# 04-WPT-IC.net
KiCad netlist of a schematic drawn in Altium Designer
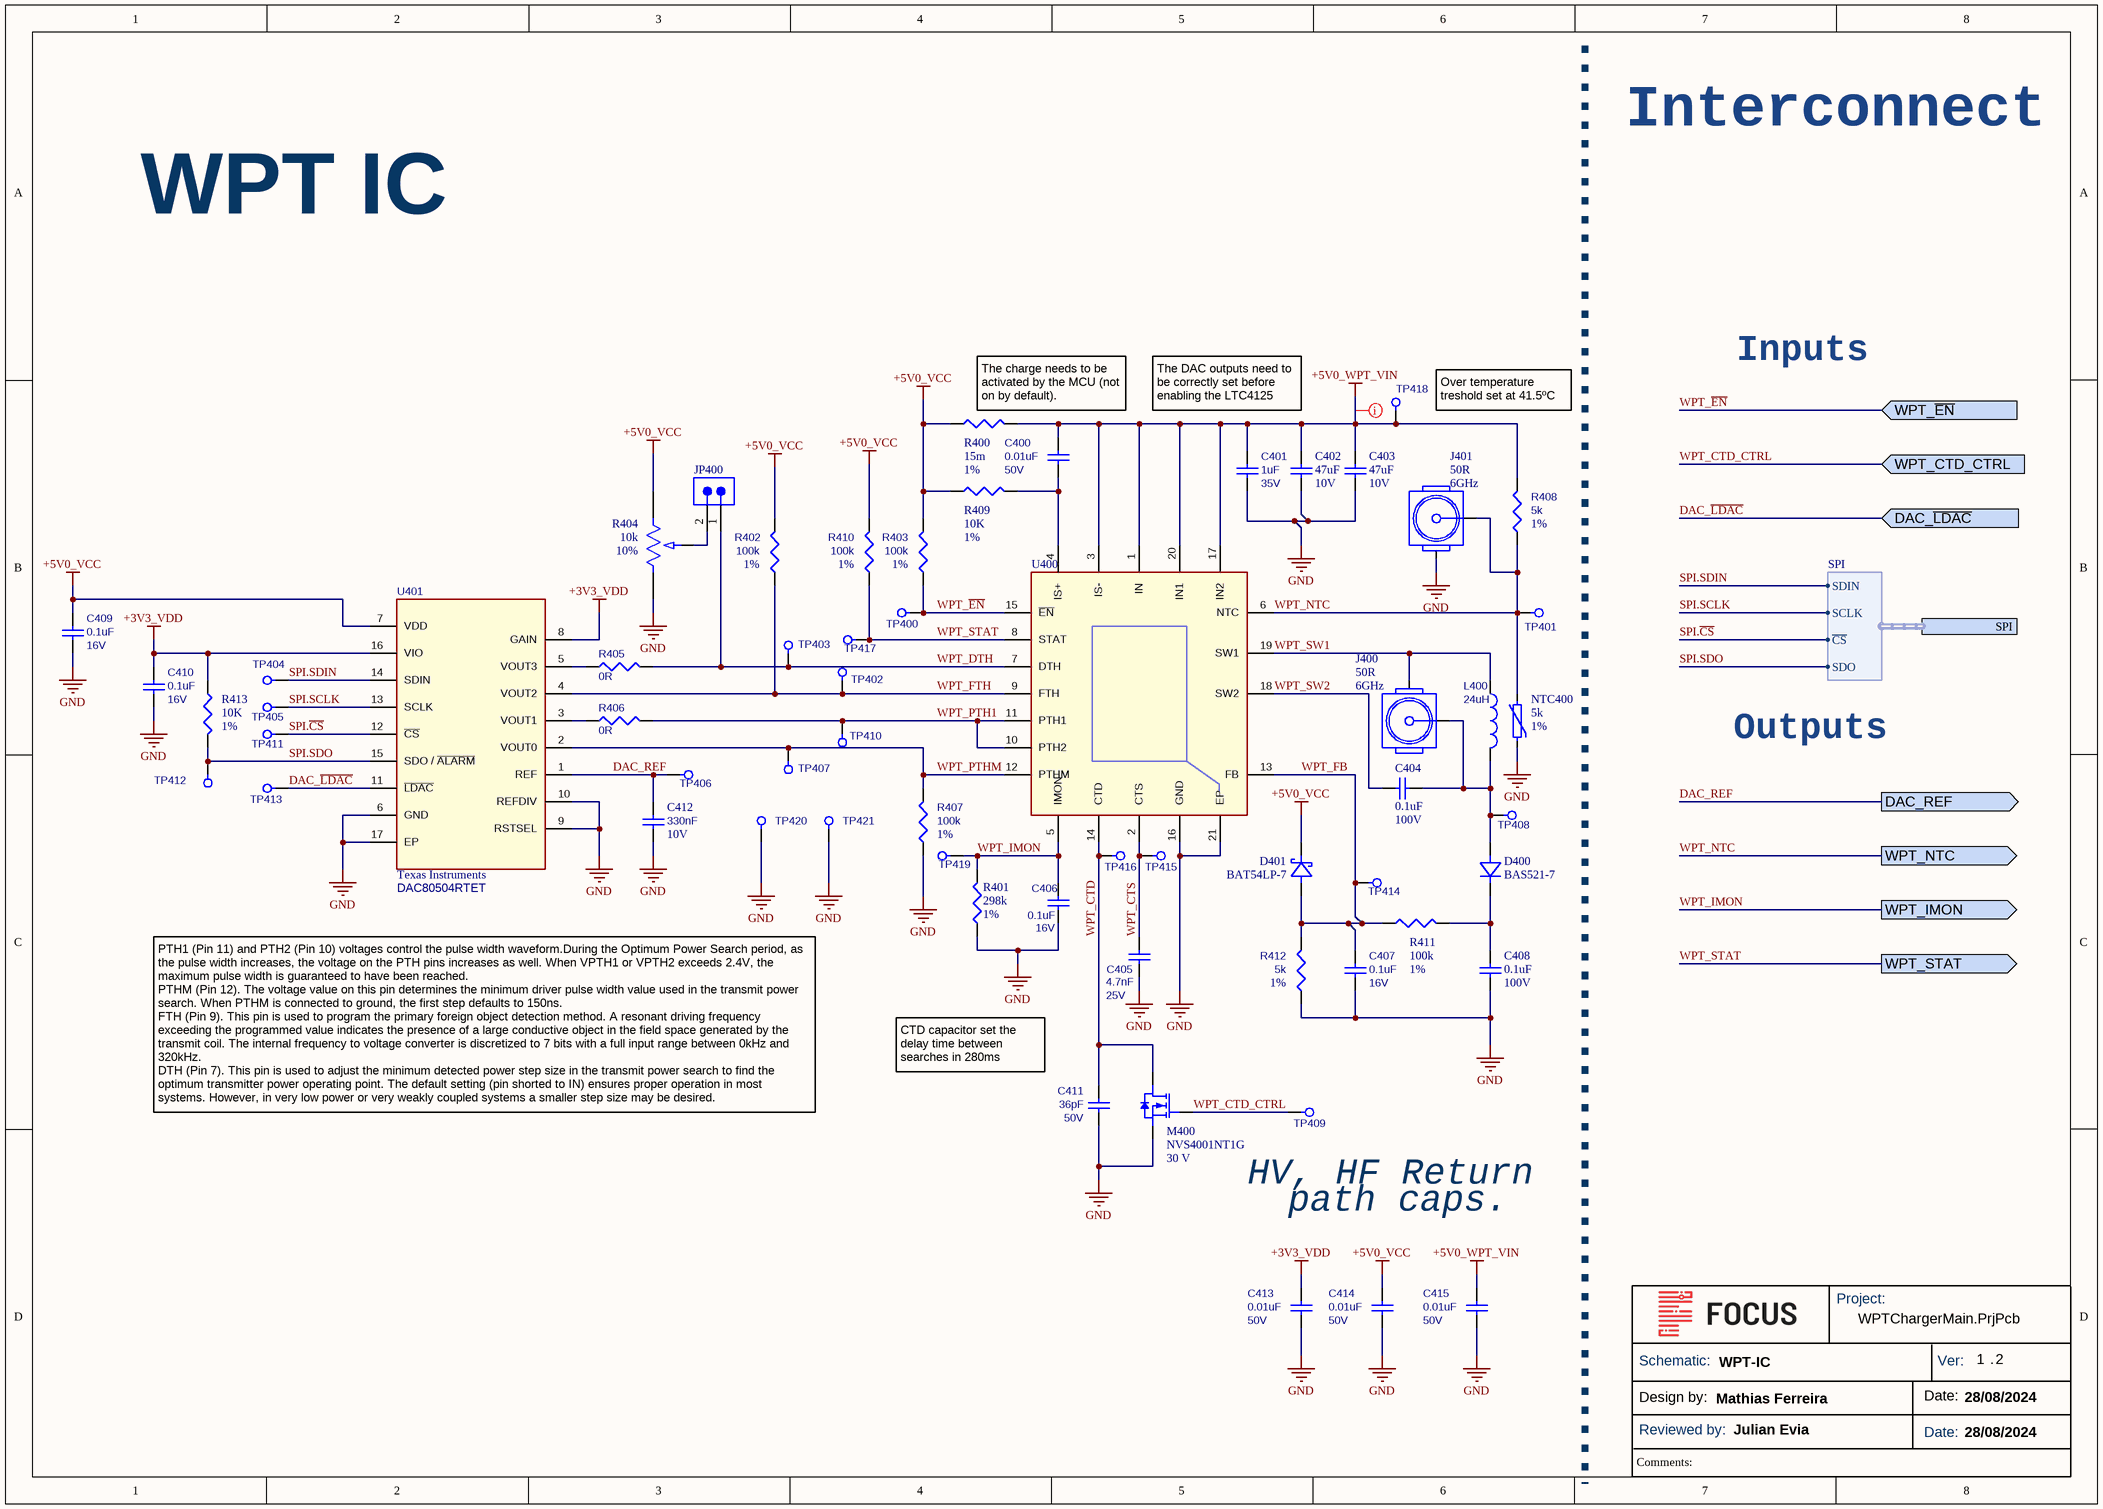
[diagram p0: 04-WPT-IC.SchDoc]

(export (version "E")
  (design (tool "Eeschema 10.0.6"))
  (components
    (comp (ref "C400")
      (value "0.01uF")
      (footprint "C0402")
      (description "Capacitor, 0.01uF, X7R, 50V, 10%, 0402, Implant-grade")
      (fields
        (field (name "MANUFACTURER") "Murata")
        (field (name "RATING") "50V")
        (field (name "MANUFACTURER PART NUMBER") "GCM155R71H103KA55J")
      )
      (libsource (lib "MP-LIBRARY") (part "GCM155R71H103KA55J"))
    )
    (comp (ref "C401")
      (value "1uF")
      (footprint "C0402")
      (description "1 µF ±10% 35V Ceramic Capacitor X5R 0402 (1005 Metric)")
      (fields
        (field (name "MANUFACTURER") "Murata")
        (field (name "MANUFACTURER PART NUMBER") "GRM155R6YA105KE11D")
        (field (name "RATING") "35V")
      )
      (libsource (lib "MP-LIBRARY") (part "GRM155R6YA105KE11D"))
    )
    (comp (ref "C402")
      (value "47uF")
      (footprint "C0805")
      (description "47 µF ±20% 10V Ceramic Capacitor X5R 0805 (2012 Metric)")
      (fields
        (field (name "MANUFACTURER") "Murata")
        (field (name "MANUFACTURER PART NUMBER") "GRM21BR61A476ME15L")
        (field (name "VOLTAGE RATING") "10V")
      )
      (libsource (lib "MP-LIBRARY") (part "GRM21BR61A476ME15L"))
    )
    (comp (ref "C403")
      (value "47uF")
      (footprint "C0805")
      (description "47 µF ±20% 10V Ceramic Capacitor X5R 0805 (2012 Metric)")
      (fields
        (field (name "MANUFACTURER") "Murata")
        (field (name "MANUFACTURER PART NUMBER") "GRM21BR61A476ME15L")
        (field (name "VOLTAGE RATING") "10V")
      )
      (libsource (lib "MP-LIBRARY") (part "GRM21BR61A476ME15L"))
    )
    (comp (ref "C404")
      (value "0.1uF")
      (footprint "C1206")
      (description "0.1 µF ±5% 100V Ceramic Capacitor C0G, NP0 1206 (3216 Metric)")
      (fields
        (field (name "MANUFACTURER") "TDK Corporation")
        (field (name "MANUFACTURER PART NUMBER") "C3216C0G2A104J160AC")
        (field (name "VOLTAGE RATING") "100V")
      )
      (libsource (lib "MP-LIBRARY") (part "C3216C0G2A104J160AC"))
    )
    (comp (ref "C405")
      (value "4.7nF")
      (footprint "C0402")
      (description "4700 pF ±10% 25V Ceramic Capacitor X7R 0402 (1005 Metric)")
      (fields
        (field (name "MANUFACTURER") "Murata")
        (field (name "MANUFACTURER PART NUMBER") "GCM155R71E472KA37D")
        (field (name "RATING") "25V")
      )
      (libsource (lib "MP-LIBRARY") (part "GCM155R71E472KA37D"))
    )
    (comp (ref "C406")
      (value "0.1uF")
      (footprint "C0402")
      (description "Capacitor, 0.1uF, X7R, 16V, 10%, 0402, Implant-grade")
      (fields
        (field (name "MANUFACTURER") "Murata")
        (field (name "MANUFACTURER PART NUMBER") "GCM155R71C104KA55")
        (field (name "RATING") "16V")
      )
      (libsource (lib "MP-LIBRARY") (part "GCM155R71C104KA55"))
    )
    (comp (ref "C407")
      (value "0.1uF")
      (footprint "C0402")
      (description "Capacitor, 0.1uF, X7R, 16V, 10%, 0402, Implant-grade")
      (fields
        (field (name "MANUFACTURER") "Murata")
        (field (name "MANUFACTURER PART NUMBER") "GCM155R71C104KA55")
        (field (name "RATING") "16V")
      )
      (libsource (lib "MP-LIBRARY") (part "GCM155R71C104KA55"))
    )
    (comp (ref "C408")
      (value "0.1uF")
      (footprint "C1206")
      (description "0.1 µF ±5% 100V Ceramic Capacitor C0G, NP0 1206 (3216 Metric)")
      (fields
        (field (name "MANUFACTURER") "TDK Corporation")
        (field (name "MANUFACTURER PART NUMBER") "C3216C0G2A104J160AC")
        (field (name "VOLTAGE RATING") "100V")
      )
      (libsource (lib "MP-LIBRARY") (part "C3216C0G2A104J160AC"))
    )
    (comp (ref "C409")
      (value "0.1uF")
      (footprint "C0402")
      (description "Capacitor, 0.1uF, X7R, 16V, 10%, 0402, Implant-grade")
      (fields
        (field (name "MANUFACTURER") "Murata")
        (field (name "MANUFACTURER PART NUMBER") "GCM155R71C104KA55")
        (field (name "RATING") "16V")
      )
      (libsource (lib "MP-LIBRARY") (part "GCM155R71C104KA55"))
    )
    (comp (ref "C410")
      (value "0.1uF")
      (footprint "C0402")
      (description "Capacitor, 0.1uF, X7R, 16V, 10%, 0402, Implant-grade")
      (fields
        (field (name "MANUFACTURER") "Murata")
        (field (name "MANUFACTURER PART NUMBER") "GCM155R71C104KA55")
        (field (name "RATING") "16V")
      )
      (libsource (lib "MP-LIBRARY") (part "GCM155R71C104KA55"))
    )
    (comp (ref "C411")
      (value "36pF")
      (footprint "C0402")
      (description "36 pF ±1% 50V Ceramic Capacitor C0G, NP0 0402 (1005 Metric)")
      (fields
        (field (name "MANUFACTURER") "Murata")
        (field (name "MANUFACTURER PART NUMBER") "GCM1555C1H360FA16D")
        (field (name "RATING") "50V")
      )
      (libsource (lib "MP-LIBRARY") (part "GCM1555C1H360FA16D"))
    )
    (comp (ref "C412")
      (value "330nF")
      (footprint "C0402")
      (fields
        (field (name "MANUFACTURER") "Murata")
        (field (name "MANUFACTURER PART NUMBER") "GRM155R61A334KE15D")
        (field (name "RATED DC VOLTAGE (URDC)") "10V")
      )
      (libsource (lib "MP-LIBRARY") (part "GRM155R61A334KE15D"))
    )
    (comp (ref "C413")
      (value "0.01uF")
      (footprint "C0402")
      (description "Capacitor, 0.01uF, X7R, 50V, 10%, 0402, Implant-grade")
      (fields
        (field (name "MANUFACTURER") "Murata")
        (field (name "RATING") "50V")
        (field (name "MANUFACTURER PART NUMBER") "GCM155R71H103KA55J")
      )
      (libsource (lib "MP-LIBRARY") (part "GCM155R71H103KA55J"))
    )
    (comp (ref "C414")
      (value "0.01uF")
      (footprint "C0402")
      (description "Capacitor, 0.01uF, X7R, 50V, 10%, 0402, Implant-grade")
      (fields
        (field (name "MANUFACTURER") "Murata")
        (field (name "RATING") "50V")
        (field (name "MANUFACTURER PART NUMBER") "GCM155R71H103KA55J")
      )
      (libsource (lib "MP-LIBRARY") (part "GCM155R71H103KA55J"))
    )
    (comp (ref "C415")
      (value "0.01uF")
      (footprint "C0402")
      (description "Capacitor, 0.01uF, X7R, 50V, 10%, 0402, Implant-grade")
      (fields
        (field (name "MANUFACTURER") "Murata")
        (field (name "RATING") "50V")
        (field (name "MANUFACTURER PART NUMBER") "GCM155R71H103KA55J")
      )
      (libsource (lib "MP-LIBRARY") (part "GCM155R71H103KA55J"))
    )
    (comp (ref "D400")
      (value "BAS521-7")
      (footprint "BAS521_SOD523")
      (description "Diode 300 V 250mA Surface Mount SOD-523")
      (fields (field (name "MANUFACTURER") "Diodes Incorporated"))
      (libsource (lib "MP-LIBRARY") (part "BAS521-7"))
    )
    (comp (ref "D401")
      (value "BAT54LP-7")
      (footprint "BAT54LP-7")
      (description "Diode 30 V 200mA Surface Mount X1-DFN1006-2")
      (fields (field (name "MANUFACTURER") "Diodes Incorporated"))
      (libsource (lib "MP-LIBRARY") (part "BAT54LP-7"))
    )
    (comp (ref "J400")
      (value "U.FL-R-SMT-1(10)")
      (footprint "FP-U_FL-R-SMT-1_10-MFG")
      (description "RF Connector, 1 Contact(s), Male, Board Mount, Surface Mount Terminal, Receptacle")
      (fields
        (field (name "MANUFACTURER") "Hirose")
        (field (name "CHARACTERISTIC IMPEDANCE") "50R")
        (field (name "OPERATING FREQUENCY-MAX") "6GHz")
      )
      (libsource (lib "MP-LIBRARY") (part "U.FL-R-SMT-1(10)"))
    )
    (comp (ref "J401")
      (value "U.FL-R-SMT-1(10)")
      (footprint "FP-U_FL-R-SMT-1_10-MFG")
      (description "RF Connector, 1 Contact(s), Male, Board Mount, Surface Mount Terminal, Receptacle")
      (fields
        (field (name "MANUFACTURER") "Hirose")
        (field (name "CHARACTERISTIC IMPEDANCE") "50R")
        (field (name "OPERATING FREQUENCY-MAX") "6GHz")
      )
      (libsource (lib "") (part "U.FL-R-SMT-1(10)_1"))
    )
    (comp (ref "JP400")
      (value "TSW-102-26-G-S")
      (footprint "SMTC-TSW-102-26-XX-S")
      (description "Conn Unshrouded Header HDR 2 POS 2.54mm Solder ST Thru-Hole")
      (fields (field (name "MANUFACTURER") "Samtec"))
      (libsource (lib "MP-LIBRARY") (part "TSW-102-26-G-S"))
    )
    (comp (ref "L400")
      (value "24uH")
      (footprint "Coil_pads-5mm-ThroughHole")
      (description "1 Coil, 2 Layer 24µH Wireless Charging Coil Transmitter 70mOhm")
      (fields (field (name "MANUFACTURER PART NUMBER") "760308100110") (field (name "MANUFACTURER") "Wurth"))
      (libsource (lib "MP-LIBRARY") (part "760308100110"))
    )
    (comp (ref "M400")
      (value "NVS4001NT1G")
      (footprint "NVS4001NT1G-SC-70-3")
      (description "N-Channel 30 V 270mA (Ta) 330mW (Ta) Surface Mount SC-70-3 (SOT323)")
      (fields (field (name "MANUFACTURER") "onsemi") (field (name "VDS BREAKDOWN") "30 V"))
      (libsource (lib "MP-LIBRARY") (part "NVS4001NT1G"))
    )
    (comp (ref "NTC400")
      (value "5k")
      (footprint "NTC0603")
      (description "NTC SMD 0603, 5KOHM, 1%, B25/85")
      (fields
        (field (name "MANUFACTURER") "Vishay Dale")
        (field (name "MANUFACTURER PART NUMBER") "NTCS0603E3502FLT")
        (field (name "TOLERANCE") "1%")
      )
      (libsource (lib "MP-LIBRARY") (part "NTCS0603E3502FLT"))
    )
    (comp (ref "R400")
      (value "15m")
      (footprint "R0603")
      (fields
        (field (name "POWER") "200mW")
        (field (name "MANUFACTURER") "Vishay Dale")
        (field (name "MANUFACTURER PART NUMBER") "WSL0603R0150FEA18")
        (field (name "TOLERANCE") "1%")
      )
      (libsource (lib "MP-LIBRARY") (part "WSL0603R0150FEA18"))
    )
    (comp (ref "R401")
      (value "298k")
      (footprint "R0402")
      (fields
        (field (name "POWER") "0.063W")
        (field (name "MANUFACTURER") "KOA Speer Electronics, Inc.")
        (field (name "MANUFACTURER PART NUMBER") "RN73R1ETTP2983F50")
        (field (name "TOLERANCE") "1%")
      )
      (libsource (lib "MP-LIBRARY") (part "RN73R1ETTP2983F50"))
    )
    (comp (ref "R402")
      (value "100k")
      (footprint "R0402")
      (description "Resistor, 100k, 1%, 0402, Implant-grade")
      (fields
        (field (name "MANUFACTURER") "Panasonic")
        (field (name "TOLERANCE") "1%")
        (field (name "MANUFACTURER PART NUMBER") "ERJ-2RKF1003X")
      )
      (libsource (lib "MP-LIBRARY") (part "ERJ-2RKF1003X"))
    )
    (comp (ref "R403")
      (value "100k")
      (footprint "R0402")
      (description "Resistor, 100k, 1%, 0402, Implant-grade")
      (fields
        (field (name "MANUFACTURER") "Panasonic")
        (field (name "TOLERANCE") "1%")
        (field (name "MANUFACTURER PART NUMBER") "ERJ-2RKF1003X")
      )
      (libsource (lib "MP-LIBRARY") (part "ERJ-2RKF1003X"))
    )
    (comp (ref "R404")
      (value "10k")
      (footprint "RES3_64W_TTE")
      (description "10 kOhms 0.25W, 1/4W PC Pins Through Hole Trimmer Potentiometer Cermet 12.0 Turn Top Adjustment")
      (fields
        (field (name "POWER") "0.25W")
        (field (name "MANUFACTURER") "TT Electronics/BI")
        (field (name "TOLERANCE") "10%")
      )
      (libsource (lib "MP-LIBRARY") (part "64WR10KLF"))
    )
    (comp (ref "R405")
      (value "0R")
      (footprint "R0402")
      (description "Resistor, Zero ohms, 40V, 40mW, 1%, 0402, Implant-grade")
      (fields (field (name "MANUFACTURER") "Panasonic") (field (name "TOLERANCE") "1%"))
      (libsource (lib "MP-LIBRARY") (part "ERJ-2GE0R00X"))
    )
    (comp (ref "R406")
      (value "0R")
      (footprint "R0402")
      (description "Resistor, Zero ohms, 40V, 40mW, 1%, 0402, Implant-grade")
      (fields (field (name "MANUFACTURER") "Panasonic") (field (name "TOLERANCE") "1%"))
      (libsource (lib "MP-LIBRARY") (part "ERJ-2GE0R00X"))
    )
    (comp (ref "R407")
      (value "100k")
      (footprint "R0402")
      (description "Resistor, 100k, 1%, 0402, Implant-grade")
      (fields
        (field (name "MANUFACTURER") "Panasonic")
        (field (name "TOLERANCE") "1%")
        (field (name "MANUFACTURER PART NUMBER") "ERJ-2RKF1003X")
      )
      (libsource (lib "MP-LIBRARY") (part "ERJ-2RKF1003X"))
    )
    (comp (ref "R408")
      (value "5k")
      (footprint "R0402")
      (description "5 kOhms ±1% 0.063W, 1/16W Chip Resistor 0402 (1005 Metric) Moisture Resistant Thick Film")
      (fields
        (field (name "MANUFACTURER") "Yageo")
        (field (name "TOLERANCE") "1%")
        (field (name "MANUFACTURER PART NUMBER") "RC0402FR-075KL")
      )
      (libsource (lib "MP-LIBRARY") (part "RC0402FR-075KL"))
    )
    (comp (ref "R409")
      (value "10K")
      (footprint "R0402")
      (description "Res Thick Film 0402 10K Ohm 1% 1/16W ±100ppm/°C Molded SMD SMD Paper T/R")
      (fields
        (field (name "TOLERANCE") "1%")
        (field (name "MANUFACTURER") "Vishay Dale")
        (field (name "MANUFACTURER PART NUMBER") "CRCW040210K0FKED")
      )
      (libsource (lib "MP-LIBRARY") (part "CRCW040210K0FKED"))
    )
    (comp (ref "R410")
      (value "100k")
      (footprint "R0402")
      (description "Resistor, 100k, 1%, 0402, Implant-grade")
      (fields
        (field (name "MANUFACTURER") "Panasonic")
        (field (name "TOLERANCE") "1%")
        (field (name "MANUFACTURER PART NUMBER") "ERJ-2RKF1003X")
      )
      (libsource (lib "MP-LIBRARY") (part "ERJ-2RKF1003X"))
    )
    (comp (ref "R411")
      (value "100k")
      (footprint "R0603")
      (description "100 kOhms ±1% 0.1W, 1/10W Chip Resistor 0603 (1608 Metric) Automotive AEC-Q200 Thick Film")
      (fields
        (field (name "MANUFACTURER") "Vishay")
        (field (name "MANUFACTURER PART NUMBER") "CRCW0603100KFKEAC")
        (field (name "TOLERANCE") "1%")
      )
      (libsource (lib "MP-LIBRARY") (part "CRCW0603100KFKEAC"))
    )
    (comp (ref "R412")
      (value "5k")
      (footprint "R0402")
      (description "5 kOhms ±1% 0.063W, 1/16W Chip Resistor 0402 (1005 Metric) Moisture Resistant Thick Film")
      (fields
        (field (name "MANUFACTURER") "Yageo")
        (field (name "TOLERANCE") "1%")
        (field (name "MANUFACTURER PART NUMBER") "RC0402FR-075KL")
      )
      (libsource (lib "MP-LIBRARY") (part "RC0402FR-075KL"))
    )
    (comp (ref "R413")
      (value "10K")
      (footprint "R0402")
      (description "Res Thick Film 0402 10K Ohm 1% 1/16W ±100ppm/°C Molded SMD SMD Paper T/R")
      (fields
        (field (name "TOLERANCE") "1%")
        (field (name "MANUFACTURER") "Vishay Dale")
        (field (name "MANUFACTURER PART NUMBER") "CRCW040210K0FKED")
      )
      (libsource (lib "MP-LIBRARY") (part "CRCW040210K0FKED"))
    )
    (comp (ref "TP400")
      (value "Test Point")
      (footprint "testpad_0.9mm")
      (description "Test pad, 0.90mm circular pad")
      (libsource (lib "MP-LIBRARY") (part "Test Point"))
    )
    (comp (ref "TP401")
      (value "Test Point")
      (footprint "testpad_0.9mm")
      (description "Test pad, 0.90mm circular pad")
      (libsource (lib "MP-LIBRARY") (part "Test Point"))
    )
    (comp (ref "TP402")
      (value "Test Point")
      (footprint "testpad_0.9mm")
      (description "Test pad, 0.90mm circular pad")
      (libsource (lib "MP-LIBRARY") (part "Test Point"))
    )
    (comp (ref "TP403")
      (value "Test Point")
      (footprint "testpad_0.9mm")
      (description "Test pad, 0.90mm circular pad")
      (libsource (lib "MP-LIBRARY") (part "Test Point"))
    )
    (comp (ref "TP404")
      (value "Test Point")
      (footprint "testpad_0.9mm")
      (description "Test pad, 0.90mm circular pad")
      (libsource (lib "MP-LIBRARY") (part "Test Point"))
    )
    (comp (ref "TP405")
      (value "Test Point")
      (footprint "testpad_0.9mm")
      (description "Test pad, 0.90mm circular pad")
      (libsource (lib "MP-LIBRARY") (part "Test Point"))
    )
    (comp (ref "TP406")
      (value "Test Point")
      (footprint "testpad_0.9mm")
      (description "Test pad, 0.90mm circular pad")
      (libsource (lib "MP-LIBRARY") (part "Test Point"))
    )
    (comp (ref "TP407")
      (value "Test Point")
      (footprint "testpad_0.9mm")
      (description "Test pad, 0.90mm circular pad")
      (libsource (lib "MP-LIBRARY") (part "Test Point"))
    )
    (comp (ref "TP408")
      (value "Test Point")
      (footprint "testpad_0.9mm")
      (description "Test pad, 0.90mm circular pad")
      (libsource (lib "MP-LIBRARY") (part "Test Point"))
    )
    (comp (ref "TP409")
      (value "Test Point")
      (footprint "testpad_0.9mm")
      (description "Test pad, 0.90mm circular pad")
      (libsource (lib "MP-LIBRARY") (part "Test Point"))
    )
    (comp (ref "TP410")
      (value "Test Point")
      (footprint "testpad_0.9mm")
      (description "Test pad, 0.90mm circular pad")
      (libsource (lib "MP-LIBRARY") (part "Test Point"))
    )
    (comp (ref "TP411")
      (value "Test Point")
      (footprint "testpad_0.9mm")
      (description "Test pad, 0.90mm circular pad")
      (libsource (lib "MP-LIBRARY") (part "Test Point"))
    )
    (comp (ref "TP412")
      (value "Test Point")
      (footprint "testpad_0.9mm")
      (description "Test pad, 0.90mm circular pad")
      (libsource (lib "MP-LIBRARY") (part "Test Point"))
    )
    (comp (ref "TP413")
      (value "Test Point")
      (footprint "testpad_0.9mm")
      (description "Test pad, 0.90mm circular pad")
      (libsource (lib "MP-LIBRARY") (part "Test Point"))
    )
    (comp (ref "TP414")
      (value "Test Point")
      (footprint "testpad_0.9mm")
      (description "Test pad, 0.90mm circular pad")
      (libsource (lib "MP-LIBRARY") (part "Test Point"))
    )
    (comp (ref "TP415")
      (value "Test Point")
      (footprint "testpad_0.9mm")
      (description "Test pad, 0.90mm circular pad")
      (libsource (lib "MP-LIBRARY") (part "Test Point"))
    )
    (comp (ref "TP416")
      (value "Test Point")
      (footprint "testpad_0.9mm")
      (description "Test pad, 0.90mm circular pad")
      (libsource (lib "MP-LIBRARY") (part "Test Point"))
    )
    (comp (ref "TP417")
      (value "Test Point")
      (footprint "testpad_0.9mm")
      (description "Test pad, 0.90mm circular pad")
      (libsource (lib "MP-LIBRARY") (part "Test Point"))
    )
    (comp (ref "TP418")
      (value "Test Point")
      (footprint "testpad_0.9mm")
      (description "Test pad, 0.90mm circular pad")
      (libsource (lib "MP-LIBRARY") (part "Test Point"))
    )
    (comp (ref "TP419")
      (value "Test Point")
      (footprint "testpad_0.9mm")
      (description "Test pad, 0.90mm circular pad")
      (libsource (lib "MP-LIBRARY") (part "Test Point"))
    )
    (comp (ref "TP420")
      (value "Test Point")
      (footprint "testpad_0.9mm")
      (description "Test pad, 0.90mm circular pad")
      (libsource (lib "MP-LIBRARY") (part "Test Point"))
    )
    (comp (ref "TP421")
      (value "Test Point")
      (footprint "testpad_0.9mm")
      (description "Test pad, 0.90mm circular pad")
      (libsource (lib "MP-LIBRARY") (part "Test Point"))
    )
    (comp (ref "U400")
      (value "LTC4125IUFD#TRPBF")
      (footprint "QFN50P400X500X80_HS-21N")
      (description "5W Autoresonant Wireless Power Transmitter PMIC 20-QFN (4x5)")
      (fields (field (name "MANUFACTURER") "Analog Devices Inc."))
      (libsource (lib "MP-LIBRARY") (part "LTC4125IUFD#TRPBF"))
    )
    (comp (ref "U401")
      (value "DAC80504RTET")
      (footprint "DAC60504BRTET_16-WQFN")
      (description "16 Bit Digital to Analog Converter 4 16-WQFN (3x3)")
      (fields (field (name "MANUFACTURER") "Texas Instruments"))
      (libsource (lib "MP-LIBRARY") (part "DAC80504RTET"))
    )
  )
  (nets
    (net (code "2") (name "+3V3_VDD") (class "Default")
      (node (ref "C410") (pin "2") (pinfunction "2_2") (pintype "passive"))
      (node (ref "C413") (pin "2") (pinfunction "2_2") (pintype "passive"))
      (node (ref "R413") (pin "1") (pinfunction "1_1") (pintype "passive"))
      (node (ref "U401") (pin "16") (pinfunction "VIO_16") (pintype "passive"))
      (node (ref "U401") (pin "8") (pinfunction "GAIN_8") (pintype "passive"))
    )
    (net (code "3") (name "+5V0_VCC") (class "Default")
      (node (ref "C409") (pin "2") (pinfunction "2_2") (pintype "passive"))
      (node (ref "C414") (pin "2") (pinfunction "2_2") (pintype "passive"))
      (node (ref "D401") (pin "1") (pinfunction "1_1") (pintype "passive"))
      (node (ref "R400") (pin "1") (pinfunction "1_1") (pintype "passive"))
      (node (ref "R402") (pin "2") (pinfunction "2_2") (pintype "passive"))
      (node (ref "R403") (pin "2") (pinfunction "2_2") (pintype "passive"))
      (node (ref "R404") (pin "1") (pinfunction "1_1") (pintype "passive"))
      (node (ref "R409") (pin "1") (pinfunction "1_1") (pintype "passive"))
      (node (ref "R410") (pin "2") (pinfunction "2_2") (pintype "passive"))
      (node (ref "U401") (pin "7") (pinfunction "VDD_7") (pintype "passive"))
    )
    (net (code "4") (name "+5V0_WPT_VIN") (class "Default")
      (node (ref "C400") (pin "2") (pinfunction "2_2") (pintype "passive"))
      (node (ref "C401") (pin "2") (pinfunction "2_2") (pintype "passive"))
      (node (ref "C402") (pin "2") (pinfunction "2_2") (pintype "passive"))
      (node (ref "C403") (pin "2") (pinfunction "2_2") (pintype "passive"))
      (node (ref "C415") (pin "2") (pinfunction "2_2") (pintype "passive"))
      (node (ref "R400") (pin "2") (pinfunction "2_2") (pintype "passive"))
      (node (ref "R408") (pin "2") (pinfunction "2_2") (pintype "passive"))
      (node (ref "TP418") (pin "1") (pinfunction "1_1") (pintype "passive"))
      (node (ref "U400") (pin "1") (pinfunction "IN_1") (pintype "passive"))
      (node (ref "U400") (pin "17") (pinfunction "IN2_17") (pintype "passive"))
      (node (ref "U400") (pin "20") (pinfunction "IN1_20") (pintype "passive"))
      (node (ref "U400") (pin "3") (pinfunction "IS-_3") (pintype "passive"))
    )
    (net (code "6") (name "/DAC_REF") (class "Default")
      (node (ref "C412") (pin "2") (pinfunction "2_2") (pintype "passive"))
      (node (ref "TP406") (pin "1") (pinfunction "1_1") (pintype "passive"))
      (node (ref "U401") (pin "1") (pinfunction "REF_1") (pintype "passive"))
    )
    (net (code "7") (name "/DAC_~{LDAC}") (class "Default")
      (node (ref "TP413") (pin "1") (pinfunction "1_1") (pintype "passive"))
      (node (ref "U401") (pin "11") (pinfunction "~{LDAC}_11") (pintype "passive"))
    )
    (net (code "8") (name "/SPI.SCLK") (class "Default")
      (node (ref "TP405") (pin "1") (pinfunction "1_1") (pintype "passive"))
      (node (ref "U401") (pin "13") (pinfunction "SCLK_13") (pintype "passive"))
    )
    (net (code "9") (name "/SPI.SDIN") (class "Default")
      (node (ref "TP404") (pin "1") (pinfunction "1_1") (pintype "passive"))
      (node (ref "U401") (pin "14") (pinfunction "SDIN_14") (pintype "passive"))
    )
    (net (code "10") (name "/SPI.SDO") (class "Default")
      (node (ref "R413") (pin "2") (pinfunction "2_2") (pintype "passive"))
      (node (ref "TP412") (pin "1") (pinfunction "1_1") (pintype "passive"))
      (node (ref "U401") (pin "15") (pinfunction "SDO_/_~{ALARM}_15") (pintype "passive"))
    )
    (net (code "11") (name "/SPI.~{CS}") (class "Default")
      (node (ref "TP411") (pin "1") (pinfunction "1_1") (pintype "passive"))
      (node (ref "U401") (pin "12") (pinfunction "~{CS}_12") (pintype "passive"))
    )
    (net (code "12") (name "/WPT_CTD") (class "Default")
      (node (ref "C411") (pin "2") (pinfunction "2_2") (pintype "passive"))
      (node (ref "M400") (pin "3") (pinfunction "D_3") (pintype "passive"))
      (node (ref "TP416") (pin "1") (pinfunction "1_1") (pintype "passive"))
      (node (ref "U400") (pin "14") (pinfunction "CTD_14") (pintype "passive"))
    )
    (net (code "13") (name "/WPT_CTD_CTRL") (class "Default")
      (node (ref "M400") (pin "1") (pinfunction "G_1") (pintype "passive"))
      (node (ref "TP409") (pin "1") (pinfunction "1_1") (pintype "passive"))
    )
    (net (code "14") (name "/WPT_CTS") (class "Default")
      (node (ref "C405") (pin "2") (pinfunction "2_2") (pintype "passive"))
      (node (ref "TP415") (pin "1") (pinfunction "1_1") (pintype "passive"))
      (node (ref "U400") (pin "2") (pinfunction "CTS_2") (pintype "passive"))
    )
    (net (code "15") (name "/WPT_DTH") (class "Default")
      (node (ref "JP400") (pin "1") (pinfunction "1_1") (pintype "passive"))
      (node (ref "R405") (pin "2") (pinfunction "2_2") (pintype "passive"))
      (node (ref "TP403") (pin "1") (pinfunction "1_1") (pintype "passive"))
      (node (ref "U400") (pin "7") (pinfunction "DTH_7") (pintype "passive"))
    )
    (net (code "16") (name "/WPT_FB") (class "Default")
      (node (ref "C407") (pin "2") (pinfunction "2_2") (pintype "passive"))
      (node (ref "D401") (pin "2") (pinfunction "2_2") (pintype "passive"))
      (node (ref "R411") (pin "1") (pinfunction "1_1") (pintype "passive"))
      (node (ref "R412") (pin "2") (pinfunction "2_2") (pintype "passive"))
      (node (ref "TP414") (pin "1") (pinfunction "1_1") (pintype "passive"))
      (node (ref "U400") (pin "13") (pinfunction "FB_13") (pintype "passive"))
    )
    (net (code "17") (name "/WPT_FTH") (class "Default")
      (node (ref "R402") (pin "1") (pinfunction "1_1") (pintype "passive"))
      (node (ref "TP402") (pin "1") (pinfunction "1_1") (pintype "passive"))
      (node (ref "U400") (pin "9") (pinfunction "FTH_9") (pintype "passive"))
      (node (ref "U401") (pin "4") (pinfunction "VOUT2_4") (pintype "passive"))
    )
    (net (code "18") (name "/WPT_IMON") (class "Default")
      (node (ref "C406") (pin "2") (pinfunction "2_2") (pintype "passive"))
      (node (ref "R401") (pin "2") (pinfunction "2_2") (pintype "passive"))
      (node (ref "TP419") (pin "1") (pinfunction "1_1") (pintype "passive"))
      (node (ref "U400") (pin "5") (pinfunction "IMON_5") (pintype "passive"))
    )
    (net (code "19") (name "/WPT_NTC") (class "Default")
      (node (ref "J401") (pin "1") (pinfunction "1_1") (pintype "passive"))
      (node (ref "NTC400") (pin "2") (pinfunction "2_2") (pintype "passive"))
      (node (ref "R408") (pin "1") (pinfunction "1_1") (pintype "passive"))
      (node (ref "TP401") (pin "1") (pinfunction "1_1") (pintype "passive"))
      (node (ref "U400") (pin "6") (pinfunction "NTC_6") (pintype "passive"))
    )
    (net (code "20") (name "/WPT_PTH1") (class "Default")
      (node (ref "R406") (pin "2") (pinfunction "2_2") (pintype "passive"))
      (node (ref "TP410") (pin "1") (pinfunction "1_1") (pintype "passive"))
      (node (ref "U400") (pin "10") (pinfunction "PTH2_10") (pintype "passive"))
      (node (ref "U400") (pin "11") (pinfunction "PTH1_11") (pintype "passive"))
    )
    (net (code "21") (name "/WPT_PTHM") (class "Default")
      (node (ref "R407") (pin "2") (pinfunction "2_2") (pintype "passive"))
      (node (ref "TP407") (pin "1") (pinfunction "1_1") (pintype "passive"))
      (node (ref "U400") (pin "12") (pinfunction "PTHM_12") (pintype "passive"))
      (node (ref "U401") (pin "2") (pinfunction "VOUT0_2") (pintype "passive"))
    )
    (net (code "22") (name "/WPT_STAT") (class "Default")
      (node (ref "R410") (pin "1") (pinfunction "1_1") (pintype "passive"))
      (node (ref "TP417") (pin "1") (pinfunction "1_1") (pintype "passive"))
      (node (ref "U400") (pin "8") (pinfunction "STAT_8") (pintype "passive"))
    )
    (net (code "23") (name "/WPT_SW1") (class "Default")
      (node (ref "J400") (pin "2") (pinfunction "2_2") (pintype "passive"))
      (node (ref "L400") (pin "2") (pinfunction "2_2") (pintype "passive"))
      (node (ref "U400") (pin "19") (pinfunction "SW1_19") (pintype "passive"))
    )
    (net (code "24") (name "/WPT_SW2") (class "Default")
      (node (ref "C404") (pin "2") (pinfunction "2_2") (pintype "passive"))
      (node (ref "U400") (pin "18") (pinfunction "SW2_18") (pintype "passive"))
    )
    (net (code "25") (name "/WPT_~{EN}") (class "Default")
      (node (ref "R403") (pin "1") (pinfunction "1_1") (pintype "passive"))
      (node (ref "TP400") (pin "1") (pinfunction "1_1") (pintype "passive"))
      (node (ref "U400") (pin "15") (pinfunction "~{EN}_15") (pintype "passive"))
    )
    (net (code "27") (name "GND") (class "Default")
      (node (ref "C401") (pin "1") (pinfunction "1_1") (pintype "passive"))
      (node (ref "C402") (pin "1") (pinfunction "1_1") (pintype "passive"))
      (node (ref "C403") (pin "1") (pinfunction "1_1") (pintype "passive"))
      (node (ref "C405") (pin "1") (pinfunction "1_1") (pintype "passive"))
      (node (ref "C406") (pin "1") (pinfunction "1_1") (pintype "passive"))
      (node (ref "C407") (pin "1") (pinfunction "1_1") (pintype "passive"))
      (node (ref "C408") (pin "1") (pinfunction "1_1") (pintype "passive"))
      (node (ref "C409") (pin "1") (pinfunction "1_1") (pintype "passive"))
      (node (ref "C410") (pin "1") (pinfunction "1_1") (pintype "passive"))
      (node (ref "C411") (pin "1") (pinfunction "1_1") (pintype "passive"))
      (node (ref "C412") (pin "1") (pinfunction "1_1") (pintype "passive"))
      (node (ref "C413") (pin "1") (pinfunction "1_1") (pintype "passive"))
      (node (ref "C414") (pin "1") (pinfunction "1_1") (pintype "passive"))
      (node (ref "C415") (pin "1") (pinfunction "1_1") (pintype "passive"))
      (node (ref "J401") (pin "2") (pinfunction "2_2") (pintype "passive"))
      (node (ref "M400") (pin "2") (pinfunction "S_2") (pintype "passive"))
      (node (ref "NTC400") (pin "1") (pinfunction "1_1") (pintype "passive"))
      (node (ref "R401") (pin "1") (pinfunction "1_1") (pintype "passive"))
      (node (ref "R404") (pin "3") (pinfunction "3_3") (pintype "passive"))
      (node (ref "R407") (pin "1") (pinfunction "1_1") (pintype "passive"))
      (node (ref "R412") (pin "1") (pinfunction "1_1") (pintype "passive"))
      (node (ref "TP420") (pin "1") (pinfunction "1_1") (pintype "passive"))
      (node (ref "TP421") (pin "1") (pinfunction "1_1") (pintype "passive"))
      (node (ref "U400") (pin "16") (pinfunction "GND_16") (pintype "passive"))
      (node (ref "U400") (pin "21") (pinfunction "EP_21") (pintype "passive"))
      (node (ref "U401") (pin "10") (pinfunction "REFDIV_10") (pintype "passive"))
      (node (ref "U401") (pin "17") (pinfunction "EP_17") (pintype "passive"))
      (node (ref "U401") (pin "6") (pinfunction "GND_6") (pintype "passive"))
      (node (ref "U401") (pin "9") (pinfunction "RSTSEL_9") (pintype "passive"))
    )
    (net (code "28") (name "Net-(C404-Pad1)") (class "Default")
      (node (ref "C404") (pin "1") (pinfunction "1_1") (pintype "passive"))
      (node (ref "D400") (pin "2") (pinfunction "2_2") (pintype "passive"))
      (node (ref "J400") (pin "1") (pinfunction "1_1") (pintype "passive"))
      (node (ref "L400") (pin "1") (pinfunction "1_1") (pintype "passive"))
      (node (ref "TP408") (pin "1") (pinfunction "1_1") (pintype "passive"))
    )
    (net (code "29") (name "Net-(C408-Pad2)") (class "Default")
      (node (ref "C408") (pin "2") (pinfunction "2_2") (pintype "passive"))
      (node (ref "D400") (pin "1") (pinfunction "1_1") (pintype "passive"))
      (node (ref "R411") (pin "2") (pinfunction "2_2") (pintype "passive"))
    )
    (net (code "30") (name "Net-(JP400-Pad2)") (class "Default")
      (node (ref "JP400") (pin "2") (pinfunction "2_2") (pintype "passive"))
      (node (ref "R404") (pin "2") (pinfunction "2_2") (pintype "passive"))
    )
    (net (code "31") (name "Net-(U400-IS+)") (class "Default")
      (node (ref "C400") (pin "1") (pinfunction "1_1") (pintype "passive"))
      (node (ref "R409") (pin "2") (pinfunction "2_2") (pintype "passive"))
      (node (ref "U400") (pin "4") (pinfunction "IS+_4") (pintype "passive"))
    )
    (net (code "32") (name "Net-(U401-VOUT1)") (class "Default")
      (node (ref "R406") (pin "1") (pinfunction "1_1") (pintype "passive"))
      (node (ref "U401") (pin "3") (pinfunction "VOUT1_3") (pintype "passive"))
    )
    (net (code "33") (name "Net-(U401-VOUT3)") (class "Default")
      (node (ref "R405") (pin "1") (pinfunction "1_1") (pintype "passive"))
      (node (ref "U401") (pin "5") (pinfunction "VOUT3_5") (pintype "passive"))
    )
  )
)
